# Risc_V.net
KiCad netlist of a schematic drawn in Altium Designer
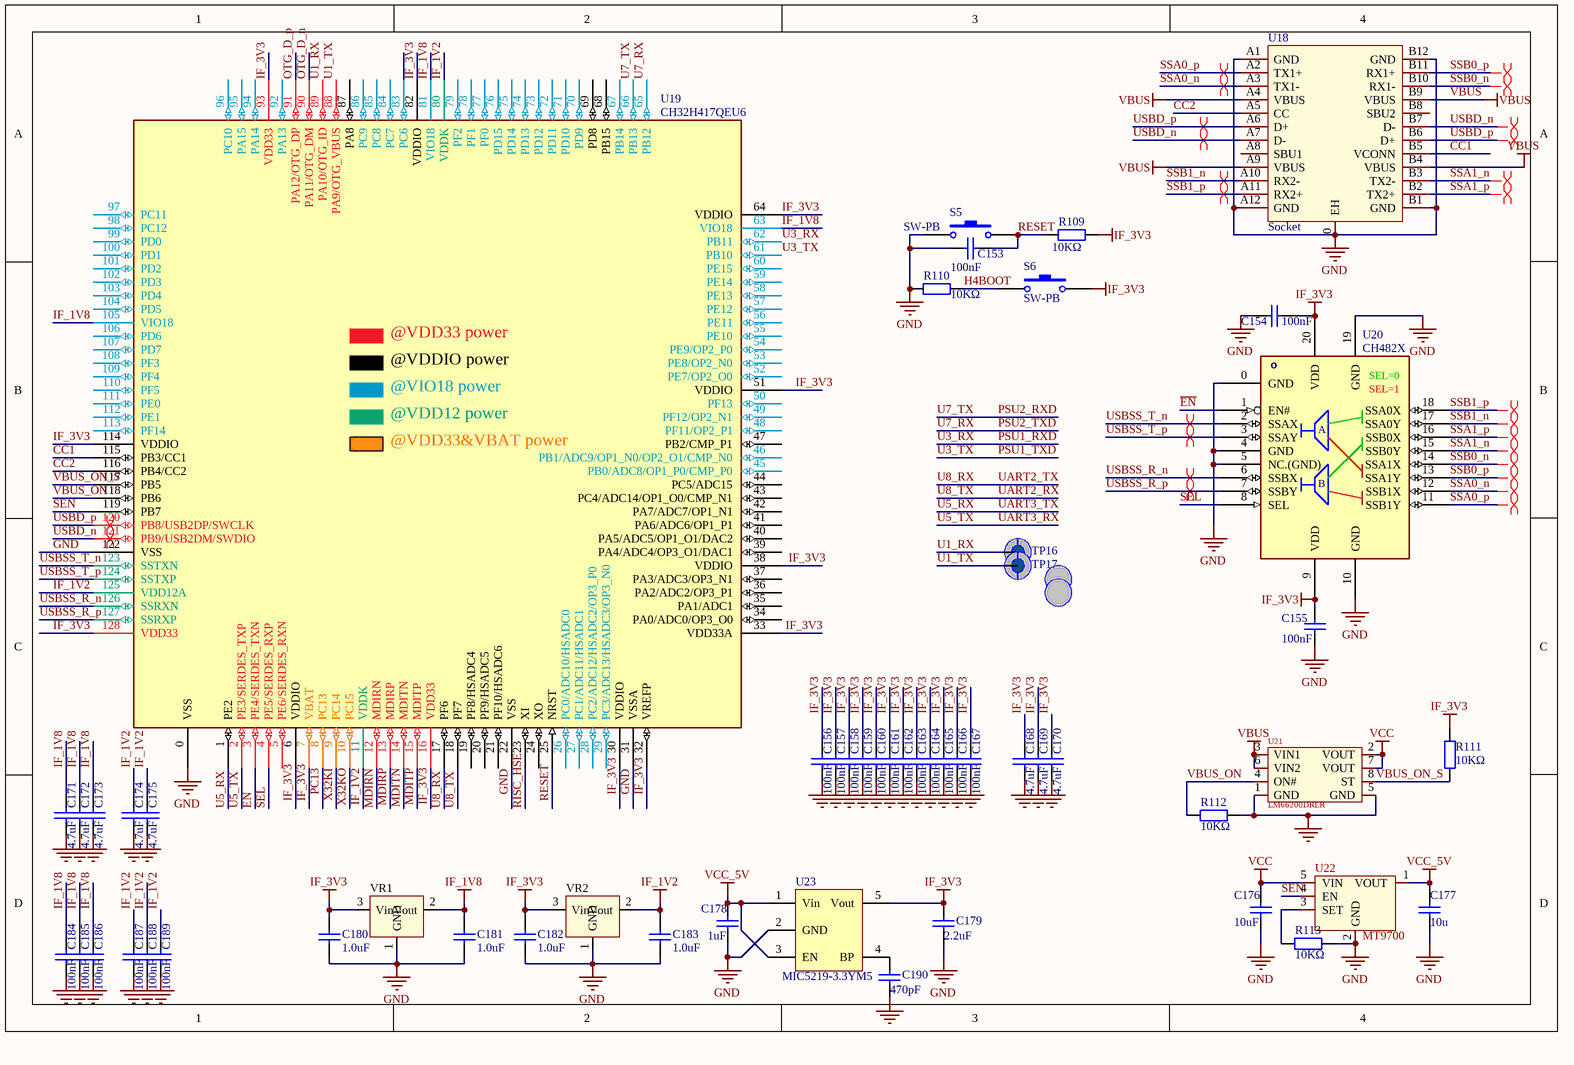
[diagram p0: Risc_V.SchDoc]

(export (version "E")
  (design (tool "Eeschema 10.0.6"))
  (components
    (comp (ref "C153")
      (value "100nF")
      (footprint "0805_C")
      (description "贴片电容")
      (libsource (lib "Miscellaneous Devices LC") (part "0402 100nF (104) 10% 16V"))
    )
    (comp (ref "C154")
      (value "100nF")
      (footprint "0201")
      (description "贴片电容")
      (libsource (lib "嘉立创标准库") (part "0402 100nF (104) 10% 16V"))
    )
    (comp (ref "C155")
      (value "100nF")
      (footprint "0201")
      (description "贴片电容")
      (libsource (lib "嘉立创标准库") (part "0402 100nF (104) 10% 16V"))
    )
    (comp (ref "C156")
      (value "100nF")
      (footprint "0201")
      (description "贴片电容")
      (libsource (lib "嘉立创标准库") (part "0402 100nF (104) 10% 16V"))
    )
    (comp (ref "C157")
      (value "100nF")
      (footprint "0201")
      (description "贴片电容")
      (libsource (lib "嘉立创标准库") (part "0402 100nF (104) 10% 16V"))
    )
    (comp (ref "C158")
      (value "100nF")
      (footprint "0201")
      (description "贴片电容")
      (libsource (lib "嘉立创标准库") (part "0402 100nF (104) 10% 16V"))
    )
    (comp (ref "C159")
      (value "100nF")
      (footprint "0201")
      (description "贴片电容")
      (libsource (lib "嘉立创标准库") (part "0402 100nF (104) 10% 16V"))
    )
    (comp (ref "C160")
      (value "100nF")
      (footprint "0201")
      (description "贴片电容")
      (libsource (lib "嘉立创标准库") (part "0402 100nF (104) 10% 16V"))
    )
    (comp (ref "C161")
      (value "100nF")
      (footprint "0201")
      (description "贴片电容")
      (libsource (lib "嘉立创标准库") (part "0402 100nF (104) 10% 16V"))
    )
    (comp (ref "C162")
      (value "100nF")
      (footprint "0201")
      (description "贴片电容")
      (libsource (lib "嘉立创标准库") (part "0402 100nF (104) 10% 16V"))
    )
    (comp (ref "C163")
      (value "100nF")
      (footprint "0201")
      (description "贴片电容")
      (libsource (lib "嘉立创标准库") (part "0402 100nF (104) 10% 16V"))
    )
    (comp (ref "C164")
      (value "100nF")
      (footprint "0201")
      (description "贴片电容")
      (libsource (lib "嘉立创标准库") (part "0402 100nF (104) 10% 16V"))
    )
    (comp (ref "C165")
      (value "100nF")
      (footprint "0201")
      (description "贴片电容")
      (libsource (lib "嘉立创标准库") (part "0402 100nF (104) 10% 16V"))
    )
    (comp (ref "C166")
      (value "100nF")
      (footprint "0201")
      (description "贴片电容")
      (libsource (lib "嘉立创标准库") (part "0402 100nF (104) 10% 16V"))
    )
    (comp (ref "C167")
      (value "100nF")
      (footprint "0201")
      (description "贴片电容")
      (libsource (lib "嘉立创标准库") (part "0402 100nF (104) 10% 16V"))
    )
    (comp (ref "C168")
      (value "4.7uF")
      (footprint "0805_C")
      (description "Capacitor")
      (libsource (lib "*") (part "CAP"))
    )
    (comp (ref "C169")
      (value "4.7uF")
      (footprint "0805_C")
      (description "Capacitor")
      (libsource (lib "*") (part "CAP"))
    )
    (comp (ref "C170")
      (value "4.7uF")
      (footprint "0805_C")
      (description "Capacitor")
      (libsource (lib "*") (part "CAP"))
    )
    (comp (ref "C171")
      (value "4.7uF")
      (footprint "0805_C")
      (description "Capacitor")
      (libsource (lib "*") (part "CAP"))
    )
    (comp (ref "C172")
      (value "4.7uF")
      (footprint "0805_C")
      (description "Capacitor")
      (libsource (lib "*") (part "CAP"))
    )
    (comp (ref "C173")
      (value "4.7uF")
      (footprint "0805_C")
      (description "Capacitor")
      (libsource (lib "*") (part "CAP"))
    )
    (comp (ref "C174")
      (value "4.7uF")
      (footprint "0805_C")
      (description "Capacitor")
      (libsource (lib "*") (part "CAP"))
    )
    (comp (ref "C175")
      (value "4.7uF")
      (footprint "0805_C")
      (description "Capacitor")
      (libsource (lib "*") (part "CAP"))
    )
    (comp (ref "C176")
      (value "10uF")
      (footprint "0805_C")
      (description "贴片电容")
      (libsource (lib "Miscellaneous Devices LC") (part "0805 10uF (106) 10% 25V"))
    )
    (comp (ref "C177")
      (value "10u")
      (footprint "0805_C")
      (description "贴片电容")
      (libsource (lib "Miscellaneous Devices LC") (part "0805 10uF (106) 10% 25V"))
    )
    (comp (ref "C178")
      (value "1uF")
      (footprint "0805_C")
      (description "贴片电容")
      (libsource (lib "Miscellaneous Devices LC") (part "0805 1uF (105) 10% 50V"))
    )
    (comp (ref "C179")
      (value "2.2uF")
      (footprint "0805_C")
      (description "贴片电容")
      (libsource (lib "Miscellaneous Devices LC") (part "0805 1uF (105) 10% 50V"))
    )
    (comp (ref "C180")
      (value "1.0uF")
      (footprint "0805_C")
      (description "贴片电容")
      (libsource (lib "Miscellaneous Devices LC") (part "0402 1.0uF (105) 10% 25V"))
    )
    (comp (ref "C181")
      (value "1.0uF")
      (footprint "0805_C")
      (description "贴片电容")
      (libsource (lib "Miscellaneous Devices LC") (part "0402 1.0uF (105) 10% 25V"))
    )
    (comp (ref "C182")
      (value "1.0uF")
      (footprint "0805_C")
      (description "贴片电容")
      (libsource (lib "Miscellaneous Devices LC") (part "0402 1.0uF (105) 10% 25V"))
    )
    (comp (ref "C183")
      (value "1.0uF")
      (footprint "0805_C")
      (description "贴片电容")
      (libsource (lib "Miscellaneous Devices LC") (part "0402 1.0uF (105) 10% 25V"))
    )
    (comp (ref "C184")
      (value "100nF")
      (footprint "0201")
      (description "贴片电容")
      (libsource (lib "嘉立创标准库") (part "0402 100nF (104) 10% 16V"))
    )
    (comp (ref "C185")
      (value "100nF")
      (footprint "0201")
      (description "贴片电容")
      (libsource (lib "嘉立创标准库") (part "0402 100nF (104) 10% 16V"))
    )
    (comp (ref "C186")
      (value "100nF")
      (footprint "0201")
      (description "贴片电容")
      (libsource (lib "嘉立创标准库") (part "0402 100nF (104) 10% 16V"))
    )
    (comp (ref "C187")
      (value "100nF")
      (footprint "0201")
      (description "贴片电容")
      (libsource (lib "嘉立创标准库") (part "0402 100nF (104) 10% 16V"))
    )
    (comp (ref "C188")
      (value "100nF")
      (footprint "0201")
      (description "贴片电容")
      (libsource (lib "嘉立创标准库") (part "0402 100nF (104) 10% 16V"))
    )
    (comp (ref "C189")
      (value "100nF")
      (footprint "0201")
      (description "贴片电容")
      (libsource (lib "嘉立创标准库") (part "0402 100nF (104) 10% 16V"))
    )
    (comp (ref "C190")
      (value "470pF")
      (footprint "0805_C")
      (description "贴片电容")
      (libsource (lib "Miscellaneous Devices LC") (part "0805 1uF (105) 10% 50V"))
    )
    (comp (ref "R109")
      (value "10KΩ")
      (footprint "0805_R")
      (description "贴片电阻")
      (libsource (lib "Miscellaneous Devices LC") (part "0402 10KΩ (1002) 1%"))
    )
    (comp (ref "R110")
      (value "10KΩ")
      (footprint "0805_R")
      (description "贴片电阻")
      (libsource (lib "Miscellaneous Devices LC") (part "0402 10KΩ (1002) 1%"))
    )
    (comp (ref "R111")
      (value "10KΩ")
      (footprint "0805_R")
      (description "贴片电阻")
      (libsource (lib "Miscellaneous Devices LC") (part "0805 10KΩ (1002) 1%"))
    )
    (comp (ref "R112")
      (value "10KΩ")
      (footprint "0201")
      (description "贴片电阻")
      (libsource (lib "") (part "0805 10KΩ (1002) 1%_1"))
    )
    (comp (ref "R113")
      (value "10KΩ")
      (footprint "0805_R")
      (description "贴片电阻")
      (libsource (lib "") (part "0805 10KΩ (1002) 1%_1"))
    )
    (comp (ref "S5")
      (value "SW-PB")
      (footprint "SW-3*4-2P")
      (description "Switch")
      (fields (field (name "PUBLISHER") "Altium Limited"))
      (libsource (lib "Miscellaneous Devices") (part "SW-PB"))
    )
    (comp (ref "S6")
      (value "SW-PB")
      (footprint "SW-3*4-2P")
      (description "Switch")
      (fields (field (name "PUBLISHER") "Altium Limited"))
      (libsource (lib "Miscellaneous Devices") (part "SW-PB"))
    )
    (comp (ref "TP16")
      (value "test-point")
      (footprint "POINT")
      (description "测试点")
      (libsource (lib "五向开关") (part "test-point"))
    )
    (comp (ref "TP17")
      (value "test-point")
      (footprint "POINT")
      (description "测试点")
      (libsource (lib "五向开关") (part "test-point"))
    )
    (comp (ref "U18")
      (value "Socket")
      (footprint "USB Type C 24pin全后贴")
      (libsource (lib "五向开关") (part "USB type C 沉板公头"))
    )
    (comp (ref "U19")
      (value "CH32H417QEU6")
      (footprint "QFN128_12.3X12.3")
      (description "RISC-V FPU HD-MCU, 384MHz, USB3.0 & PD, 100M Ethernet, DVP, SDMMC, QSPI, OPA, ADC, DAC")
      (libsource (lib "DHXXXSCH") (part "CH32H417QET6"))
    )
    (comp (ref "U20")
      (value "CH482X")
      (footprint "QFN20_2.5X4.5")
      (description "DP/PCIe/SATA/USB3.0/USB3.2 Differential Switch, QPDT")
      (libsource (lib "CHXXX") (part "CH482X"))
    )
    (comp (ref "U21")
      (value "LM66200DRLR")
      (footprint "SOT-583-8_L2.1-W1.2-P0.50-LS1.6-BL")
      (description "理想二极管")
      (fields (field (name "MANUFACTURER") "TI(德州仪器)"))
      (libsource (lib "五向开关") (part "LM66200DRLR"))
    )
    (comp (ref "U22")
      (value "MT9700")
      (footprint "SOT-23-5")
      (fields (field (name "MANUFACTURER") "西安航天民芯"))
      (libsource (lib "五向开关") (part "MT9700"))
    )
    (comp (ref "U23")
      (value "MIC5219-3.3YM5")
      (footprint "SOT-23-5")
      (description "3.3v低压差稳压芯片")
      (libsource (lib "五向开关") (part "RT9193-33"))
    )
    (comp (ref "VR1")
      (value "XC6206P332MR-G")
      (footprint "SOT-23-3_L2.9-W1.6-P1.90-LS2.8-BR")
      (description "通用LDO")
      (fields (field (name "MANUFACTURER") "TOREX(特瑞仕)"))
      (libsource (lib "五向开关") (part "XC6206P332MR-G_C5446"))
    )
    (comp (ref "VR2")
      (value "XC6206P332MR-G")
      (footprint "SOT-23-3_L2.9-W1.6-P1.90-LS2.8-BR")
      (description "通用LDO")
      (fields (field (name "MANUFACTURER") "TOREX(特瑞仕)"))
      (libsource (lib "五向开关") (part "XC6206P332MR-G_C5446"))
    )
  )
  (nets
    (net (code "1") (name "/CC1") (class "Default")
      (node (ref "U18") (pin "B5") (pinfunction "VCONN_B5") (pintype "passive"))
      (node (ref "U19") (pin "115") (pinfunction "PB3/CC1_115") (pintype "bidirectional"))
    )
    (net (code "2") (name "/CC2") (class "Default")
      (node (ref "U18") (pin "A5") (pinfunction "CC_A5") (pintype "passive"))
      (node (ref "U19") (pin "116") (pinfunction "PB4/CC2_116") (pintype "bidirectional"))
    )
    (net (code "3") (name "/H4BOOT") (class "Default")
      (node (ref "R110") (pin "2") (pinfunction "2_2") (pintype "passive"))
      (node (ref "S6") (pin "1") (pinfunction "1_1") (pintype "passive"))
    )
    (net (code "4") (name "/MDIRN") (class "Default")
      (node (ref "U19") (pin "12") (pinfunction "MDIRN_12") (pintype "bidirectional"))
    )
    (net (code "5") (name "/MDIRP") (class "Default")
      (node (ref "U19") (pin "13") (pinfunction "MDIRP_13") (pintype "bidirectional"))
    )
    (net (code "6") (name "/MDITN") (class "Default")
      (node (ref "U19") (pin "14") (pinfunction "MDITN_14") (pintype "bidirectional"))
    )
    (net (code "7") (name "/MDITP") (class "Default")
      (node (ref "U19") (pin "15") (pinfunction "MDITP_15") (pintype "bidirectional"))
    )
    (net (code "8") (name "/OTG_D_n") (class "Default")
      (node (ref "U19") (pin "90") (pinfunction "PA11/OTG_DM_90") (pintype "bidirectional"))
    )
    (net (code "9") (name "/OTG_D_p") (class "Default")
      (node (ref "U19") (pin "91") (pinfunction "PA12/OTG_DP_91") (pintype "bidirectional"))
    )
    (net (code "10") (name "/PC13") (class "Default")
      (node (ref "U19") (pin "8") (pinfunction "PC13_8") (pintype "bidirectional"))
    )
    (net (code "11") (name "/PSU1_RXD") (class "Default")
      (node (ref "U19") (pin "62") (pinfunction "PB11_62") (pintype "bidirectional"))
    )
    (net (code "12") (name "/PSU1_TXD") (class "Default")
      (node (ref "U19") (pin "61") (pinfunction "PB10_61") (pintype "bidirectional"))
    )
    (net (code "13") (name "/PSU2_RXD") (class "Default")
      (node (ref "U19") (pin "66") (pinfunction "PB13_66") (pintype "bidirectional"))
    )
    (net (code "14") (name "/PSU2_TXD") (class "Default")
      (node (ref "U19") (pin "65") (pinfunction "PB12_65") (pintype "bidirectional"))
    )
    (net (code "15") (name "/RESET") (class "Default")
      (node (ref "C153") (pin "2") (pinfunction "2_2") (pintype "passive"))
      (node (ref "R109") (pin "1") (pinfunction "1_1") (pintype "passive"))
      (node (ref "S5") (pin "2") (pinfunction "2_2") (pintype "passive"))
      (node (ref "U19") (pin "25") (pinfunction "NRST_25") (pintype "input"))
    )
    (net (code "16") (name "/RISC_HSE") (class "Default")
      (node (ref "U19") (pin "23") (pinfunction "XI_23") (pintype "bidirectional"))
    )
    (net (code "17") (name "/SEL") (class "Default")
      (node (ref "U19") (pin "4") (pinfunction "PE5/SERDES_RXP_4") (pintype "bidirectional"))
      (node (ref "U20") (pin "8") (pinfunction "SEL_8") (pintype "input"))
    )
    (net (code "18") (name "/SEN") (class "Default")
      (node (ref "U19") (pin "119") (pinfunction "PB7_119") (pintype "bidirectional"))
      (node (ref "U22") (pin "4") (pinfunction "EN_4") (pintype "passive"))
    )
    (net (code "19") (name "/SSA0_n") (class "Default")
      (node (ref "U18") (pin "A3") (pinfunction "TX1-_A3") (pintype "passive"))
      (node (ref "U20") (pin "12") (pinfunction "SSB1X_12") (pintype "bidirectional"))
    )
    (net (code "20") (name "/SSA0_p") (class "Default")
      (node (ref "U18") (pin "A2") (pinfunction "TX1+_A2") (pintype "passive"))
      (node (ref "U20") (pin "11") (pinfunction "SSB1Y_11") (pintype "bidirectional"))
    )
    (net (code "21") (name "/SSA1_n") (class "Default")
      (node (ref "U18") (pin "B3") (pinfunction "TX2-_B3") (pintype "passive"))
      (node (ref "U20") (pin "15") (pinfunction "SSB0Y_15") (pintype "bidirectional"))
    )
    (net (code "22") (name "/SSA1_p") (class "Default")
      (node (ref "U18") (pin "B2") (pinfunction "TX2+_B2") (pintype "passive"))
      (node (ref "U20") (pin "16") (pinfunction "SSB0X_16") (pintype "bidirectional"))
    )
    (net (code "23") (name "/SSB0_n") (class "Default")
      (node (ref "U18") (pin "B10") (pinfunction "RX1-_B10") (pintype "passive"))
      (node (ref "U20") (pin "14") (pinfunction "SSA1X_14") (pintype "bidirectional"))
    )
    (net (code "24") (name "/SSB0_p") (class "Default")
      (node (ref "U18") (pin "B11") (pinfunction "RX1+_B11") (pintype "passive"))
      (node (ref "U20") (pin "13") (pinfunction "SSA1Y_13") (pintype "bidirectional"))
    )
    (net (code "25") (name "/SSB1_n") (class "Default")
      (node (ref "U18") (pin "A10") (pinfunction "RX2-_A10") (pintype "passive"))
      (node (ref "U20") (pin "17") (pinfunction "SSA0Y_17") (pintype "bidirectional"))
    )
    (net (code "26") (name "/SSB1_p") (class "Default")
      (node (ref "U18") (pin "A11") (pinfunction "RX2+_A11") (pintype "passive"))
      (node (ref "U20") (pin "18") (pinfunction "SSA0X_18") (pintype "bidirectional"))
    )
    (net (code "27") (name "/U1_RX") (class "Default")
      (node (ref "TP16") (pin "1") (pinfunction "point_1") (pintype "passive"))
      (node (ref "U19") (pin "89") (pinfunction "PA10/OTG_ID_89") (pintype "bidirectional"))
    )
    (net (code "28") (name "/U1_TX") (class "Default")
      (node (ref "TP17") (pin "1") (pinfunction "point_1") (pintype "passive"))
      (node (ref "U19") (pin "88") (pinfunction "PA9/OTG_VBUS_88") (pintype "bidirectional"))
    )
    (net (code "29") (name "/U5_RX") (class "Default")
      (node (ref "U19") (pin "1") (pinfunction "PE2_1") (pintype "bidirectional"))
    )
    (net (code "30") (name "/U5_TX") (class "Default")
      (node (ref "U19") (pin "2") (pinfunction "PE3/SERDES_TXP_2") (pintype "bidirectional"))
    )
    (net (code "31") (name "/U8_RX") (class "Default")
      (node (ref "U19") (pin "17") (pinfunction "PF6_17") (pintype "bidirectional"))
    )
    (net (code "32") (name "/U8_TX") (class "Default")
      (node (ref "U19") (pin "18") (pinfunction "PF7_18") (pintype "bidirectional"))
    )
    (net (code "33") (name "/USBD_n") (class "Default")
      (node (ref "U18") (pin "A7") (pinfunction "D-_A7") (pintype "passive"))
      (node (ref "U18") (pin "B7") (pinfunction "D-_B7") (pintype "passive"))
      (node (ref "U19") (pin "121") (pinfunction "PB9/USB2DM/SWDIO_121") (pintype "bidirectional"))
    )
    (net (code "34") (name "/USBD_p") (class "Default")
      (node (ref "U18") (pin "A6") (pinfunction "D+_A6") (pintype "passive"))
      (node (ref "U18") (pin "B6") (pinfunction "D+_B6") (pintype "passive"))
      (node (ref "U19") (pin "120") (pinfunction "PB8/USB2DP/SWCLK_120") (pintype "bidirectional"))
    )
    (net (code "35") (name "/USBSS_R_n") (class "Default")
      (node (ref "U19") (pin "126") (pinfunction "SSRXN_126") (pintype "bidirectional"))
      (node (ref "U20") (pin "6") (pinfunction "SSBX_6") (pintype "bidirectional"))
    )
    (net (code "36") (name "/USBSS_R_p") (class "Default")
      (node (ref "U19") (pin "127") (pinfunction "SSRXP_127") (pintype "bidirectional"))
      (node (ref "U20") (pin "7") (pinfunction "SSBY_7") (pintype "bidirectional"))
    )
    (net (code "37") (name "/USBSS_T_n") (class "Default")
      (node (ref "U19") (pin "123") (pinfunction "SSTXN_123") (pintype "bidirectional"))
      (node (ref "U20") (pin "2") (pinfunction "SSAX_2") (pintype "bidirectional"))
    )
    (net (code "38") (name "/USBSS_T_p") (class "Default")
      (node (ref "U19") (pin "124") (pinfunction "SSTXP_124") (pintype "bidirectional"))
      (node (ref "U20") (pin "3") (pinfunction "SSAY_3") (pintype "bidirectional"))
    )
    (net (code "39") (name "/VBUS_ON") (class "Default")
      (node (ref "R112") (pin "2") (pinfunction "2_2") (pintype "passive"))
      (node (ref "U19") (pin "118") (pinfunction "PB6_118") (pintype "bidirectional"))
      (node (ref "U21") (pin "4") (pinfunction "ON#_4") (pintype "passive"))
    )
    (net (code "40") (name "/VBUS_ON_S") (class "Default")
      (node (ref "R111") (pin "1") (pinfunction "1_1") (pintype "passive"))
      (node (ref "U19") (pin "117") (pinfunction "PB5_117") (pintype "bidirectional"))
      (node (ref "U21") (pin "8") (pinfunction "ST_8") (pintype "passive"))
    )
    (net (code "41") (name "/X32KI") (class "Default")
      (node (ref "U19") (pin "9") (pinfunction "PC14_9") (pintype "bidirectional"))
    )
    (net (code "42") (name "/X32KO") (class "Default")
      (node (ref "U19") (pin "10") (pinfunction "PC15_10") (pintype "bidirectional"))
    )
    (net (code "43") (name "/~{EN}") (class "Default")
      (node (ref "U19") (pin "3") (pinfunction "PE4/SERDES_TXN_3") (pintype "bidirectional"))
      (node (ref "U20") (pin "1") (pinfunction "EN#_1") (pintype "input"))
    )
    (net (code "44") (name "GND") (class "Default")
      (node (ref "C153") (pin "1") (pinfunction "1_1") (pintype "passive"))
      (node (ref "C154") (pin "2") (pinfunction "2_2") (pintype "passive"))
      (node (ref "C155") (pin "1") (pinfunction "1_1") (pintype "passive"))
      (node (ref "C156") (pin "2") (pinfunction "2_2") (pintype "passive"))
      (node (ref "C157") (pin "1") (pinfunction "1_1") (pintype "passive"))
      (node (ref "C158") (pin "2") (pinfunction "2_2") (pintype "passive"))
      (node (ref "C159") (pin "2") (pinfunction "2_2") (pintype "passive"))
      (node (ref "C160") (pin "1") (pinfunction "1_1") (pintype "passive"))
      (node (ref "C161") (pin "2") (pinfunction "2_2") (pintype "passive"))
      (node (ref "C162") (pin "1") (pinfunction "1_1") (pintype "passive"))
      (node (ref "C163") (pin "2") (pinfunction "2_2") (pintype "passive"))
      (node (ref "C164") (pin "2") (pinfunction "2_2") (pintype "passive"))
      (node (ref "C165") (pin "1") (pinfunction "1_1") (pintype "passive"))
      (node (ref "C166") (pin "1") (pinfunction "1_1") (pintype "passive"))
      (node (ref "C167") (pin "1") (pinfunction "1_1") (pintype "passive"))
      (node (ref "C168") (pin "2") (pinfunction "2_2") (pintype "passive"))
      (node (ref "C169") (pin "2") (pinfunction "2_2") (pintype "passive"))
      (node (ref "C170") (pin "2") (pinfunction "2_2") (pintype "passive"))
      (node (ref "C171") (pin "2") (pinfunction "2_2") (pintype "passive"))
      (node (ref "C172") (pin "1") (pinfunction "1_1") (pintype "passive"))
      (node (ref "C173") (pin "2") (pinfunction "2_2") (pintype "passive"))
      (node (ref "C174") (pin "2") (pinfunction "2_2") (pintype "passive"))
      (node (ref "C175") (pin "1") (pinfunction "1_1") (pintype "passive"))
      (node (ref "C176") (pin "1") (pinfunction "1_1") (pintype "passive"))
      (node (ref "C177") (pin "1") (pinfunction "1_1") (pintype "passive"))
      (node (ref "C178") (pin "1") (pinfunction "1_1") (pintype "passive"))
      (node (ref "C179") (pin "1") (pinfunction "1_1") (pintype "passive"))
      (node (ref "C180") (pin "1") (pinfunction "1_1") (pintype "passive"))
      (node (ref "C181") (pin "1") (pinfunction "1_1") (pintype "passive"))
      (node (ref "C182") (pin "1") (pinfunction "1_1") (pintype "passive"))
      (node (ref "C183") (pin "1") (pinfunction "1_1") (pintype "passive"))
      (node (ref "C184") (pin "1") (pinfunction "1_1") (pintype "passive"))
      (node (ref "C185") (pin "1") (pinfunction "1_1") (pintype "passive"))
      (node (ref "C186") (pin "2") (pinfunction "2_2") (pintype "passive"))
      (node (ref "C187") (pin "1") (pinfunction "1_1") (pintype "passive"))
      (node (ref "C188") (pin "1") (pinfunction "1_1") (pintype "passive"))
      (node (ref "C189") (pin "1") (pinfunction "1_1") (pintype "passive"))
      (node (ref "C190") (pin "1") (pinfunction "1_1") (pintype "passive"))
      (node (ref "R110") (pin "1") (pinfunction "1_1") (pintype "passive"))
      (node (ref "R112") (pin "1") (pinfunction "1_1") (pintype "passive"))
      (node (ref "R113") (pin "1") (pinfunction "1_1") (pintype "passive"))
      (node (ref "S5") (pin "1") (pinfunction "1_1") (pintype "passive"))
      (node (ref "U18") (pin "0") (pinfunction "EH_0") (pintype "passive"))
      (node (ref "U18") (pin "A1") (pinfunction "GND_A1") (pintype "passive"))
      (node (ref "U18") (pin "A12") (pinfunction "GND_A12") (pintype "passive"))
      (node (ref "U18") (pin "B1") (pinfunction "GND_B1") (pintype "passive"))
      (node (ref "U18") (pin "B12") (pinfunction "GND_B12") (pintype "passive"))
      (node (ref "U19") (pin "0") (pinfunction "VSS_0") (pintype "power_in"))
      (node (ref "U19") (pin "122") (pinfunction "VSS_122") (pintype "power_in"))
      (node (ref "U19") (pin "22") (pinfunction "VSS_22") (pintype "power_in"))
      (node (ref "U19") (pin "31") (pinfunction "VSSA_31") (pintype "power_in"))
      (node (ref "U20") (pin "0") (pinfunction "GND_0") (pintype "power_in"))
      (node (ref "U20") (pin "10") (pinfunction "GND_10") (pintype "power_in"))
      (node (ref "U20") (pin "19") (pinfunction "GND_19") (pintype "power_in"))
      (node (ref "U20") (pin "4") (pinfunction "GND_4") (pintype "power_in"))
      (node (ref "U20") (pin "5") (pinfunction "NC.(GND)_5") (pintype "passive"))
      (node (ref "U21") (pin "1") (pinfunction "GND_1") (pintype "passive"))
      (node (ref "U21") (pin "5") (pinfunction "GND_5") (pintype "passive"))
      (node (ref "U22") (pin "2") (pinfunction "GND_2") (pintype "passive"))
      (node (ref "U23") (pin "2") (pinfunction "GND_2") (pintype "passive"))
      (node (ref "VR1") (pin "1") (pinfunction "GND_1") (pintype "passive"))
      (node (ref "VR2") (pin "1") (pinfunction "GND_1") (pintype "passive"))
    )
    (net (code "45") (name "IF_1V2") (class "Default")
      (node (ref "C174") (pin "1") (pinfunction "1_1") (pintype "passive"))
      (node (ref "C175") (pin "2") (pinfunction "2_2") (pintype "passive"))
      (node (ref "C183") (pin "2") (pinfunction "2_2") (pintype "passive"))
      (node (ref "C187") (pin "2") (pinfunction "2_2") (pintype "passive"))
      (node (ref "C188") (pin "2") (pinfunction "2_2") (pintype "passive"))
      (node (ref "C189") (pin "2") (pinfunction "2_2") (pintype "passive"))
      (node (ref "U19") (pin "11") (pinfunction "VDDK_11") (pintype "power_in"))
      (node (ref "U19") (pin "125") (pinfunction "VDD12A_125") (pintype "power_in"))
      (node (ref "U19") (pin "80") (pinfunction "VDDK_80") (pintype "power_in"))
      (node (ref "VR2") (pin "2") (pinfunction "Vout_2") (pintype "passive"))
    )
    (net (code "46") (name "IF_1V8") (class "Default")
      (node (ref "C171") (pin "1") (pinfunction "1_1") (pintype "passive"))
      (node (ref "C172") (pin "2") (pinfunction "2_2") (pintype "passive"))
      (node (ref "C173") (pin "1") (pinfunction "1_1") (pintype "passive"))
      (node (ref "C181") (pin "2") (pinfunction "2_2") (pintype "passive"))
      (node (ref "C184") (pin "2") (pinfunction "2_2") (pintype "passive"))
      (node (ref "C185") (pin "2") (pinfunction "2_2") (pintype "passive"))
      (node (ref "C186") (pin "1") (pinfunction "1_1") (pintype "passive"))
      (node (ref "U19") (pin "105") (pinfunction "VIO18_105") (pintype "power_in"))
      (node (ref "U19") (pin "63") (pinfunction "VIO18_63") (pintype "power_in"))
      (node (ref "U19") (pin "81") (pinfunction "VIO18_81") (pintype "power_in"))
      (node (ref "VR1") (pin "2") (pinfunction "Vout_2") (pintype "passive"))
    )
    (net (code "47") (name "IF_3V3") (class "Default")
      (node (ref "C154") (pin "1") (pinfunction "1_1") (pintype "passive"))
      (node (ref "C155") (pin "2") (pinfunction "2_2") (pintype "passive"))
      (node (ref "C156") (pin "1") (pinfunction "1_1") (pintype "passive"))
      (node (ref "C157") (pin "2") (pinfunction "2_2") (pintype "passive"))
      (node (ref "C158") (pin "1") (pinfunction "1_1") (pintype "passive"))
      (node (ref "C159") (pin "1") (pinfunction "1_1") (pintype "passive"))
      (node (ref "C160") (pin "2") (pinfunction "2_2") (pintype "passive"))
      (node (ref "C161") (pin "1") (pinfunction "1_1") (pintype "passive"))
      (node (ref "C162") (pin "2") (pinfunction "2_2") (pintype "passive"))
      (node (ref "C163") (pin "1") (pinfunction "1_1") (pintype "passive"))
      (node (ref "C164") (pin "1") (pinfunction "1_1") (pintype "passive"))
      (node (ref "C165") (pin "2") (pinfunction "2_2") (pintype "passive"))
      (node (ref "C166") (pin "2") (pinfunction "2_2") (pintype "passive"))
      (node (ref "C167") (pin "2") (pinfunction "2_2") (pintype "passive"))
      (node (ref "C168") (pin "1") (pinfunction "1_1") (pintype "passive"))
      (node (ref "C169") (pin "1") (pinfunction "1_1") (pintype "passive"))
      (node (ref "C170") (pin "1") (pinfunction "1_1") (pintype "passive"))
      (node (ref "C179") (pin "2") (pinfunction "2_2") (pintype "passive"))
      (node (ref "C180") (pin "2") (pinfunction "2_2") (pintype "passive"))
      (node (ref "C182") (pin "2") (pinfunction "2_2") (pintype "passive"))
      (node (ref "R109") (pin "2") (pinfunction "2_2") (pintype "passive"))
      (node (ref "R111") (pin "2") (pinfunction "2_2") (pintype "passive"))
      (node (ref "S6") (pin "2") (pinfunction "2_2") (pintype "passive"))
      (node (ref "U19") (pin "114") (pinfunction "VDDIO_114") (pintype "power_in"))
      (node (ref "U19") (pin "128") (pinfunction "VDD33_128") (pintype "power_in"))
      (node (ref "U19") (pin "16") (pinfunction "VDD33_16") (pintype "power_in"))
      (node (ref "U19") (pin "30") (pinfunction "VDDIO_30") (pintype "power_in"))
      (node (ref "U19") (pin "32") (pinfunction "VREFP_32") (pintype "bidirectional"))
      (node (ref "U19") (pin "33") (pinfunction "VDD33A_33") (pintype "power_in"))
      (node (ref "U19") (pin "38") (pinfunction "VDDIO_38") (pintype "power_in"))
      (node (ref "U19") (pin "51") (pinfunction "VDDIO_51") (pintype "power_in"))
      (node (ref "U19") (pin "6") (pinfunction "VDDIO_6") (pintype "power_in"))
      (node (ref "U19") (pin "64") (pinfunction "VDDIO_64") (pintype "power_in"))
      (node (ref "U19") (pin "7") (pinfunction "VBAT_7") (pintype "bidirectional"))
      (node (ref "U19") (pin "82") (pinfunction "VDDIO_82") (pintype "power_in"))
      (node (ref "U19") (pin "93") (pinfunction "VDD33_93") (pintype "power_in"))
      (node (ref "U20") (pin "20") (pinfunction "VDD_20") (pintype "power_in"))
      (node (ref "U20") (pin "9") (pinfunction "VDD_9") (pintype "power_in"))
      (node (ref "U23") (pin "5") (pinfunction "Vout_5") (pintype "passive"))
      (node (ref "VR1") (pin "3") (pinfunction "Vin_3") (pintype "passive"))
      (node (ref "VR2") (pin "3") (pinfunction "Vin_3") (pintype "passive"))
    )
    (net (code "48") (name "Net-(U22-SET)") (class "Default")
      (node (ref "R113") (pin "2") (pinfunction "2_2") (pintype "passive"))
      (node (ref "U22") (pin "3") (pinfunction "SET_3") (pintype "passive"))
    )
    (net (code "49") (name "Net-(U23-BP)") (class "Default")
      (node (ref "C190") (pin "2") (pinfunction "2_2") (pintype "passive"))
      (node (ref "U23") (pin "4") (pinfunction "BP_4") (pintype "passive"))
    )
    (net (code "50") (name "VBUS") (class "Default")
      (node (ref "U18") (pin "A4") (pinfunction "VBUS_A4") (pintype "passive"))
      (node (ref "U18") (pin "A9") (pinfunction "VBUS_A9") (pintype "passive"))
      (node (ref "U18") (pin "B4") (pinfunction "VBUS_B4") (pintype "passive"))
      (node (ref "U18") (pin "B9") (pinfunction "VBUS_B9") (pintype "passive"))
      (node (ref "U21") (pin "3") (pinfunction "VIN1_3") (pintype "passive"))
      (node (ref "U21") (pin "6") (pinfunction "VIN2_6") (pintype "passive"))
    )
    (net (code "51") (name "VCC") (class "Default")
      (node (ref "C176") (pin "2") (pinfunction "2_2") (pintype "passive"))
      (node (ref "U21") (pin "2") (pinfunction "VOUT_2") (pintype "passive"))
      (node (ref "U21") (pin "7") (pinfunction "VOUT_7") (pintype "passive"))
      (node (ref "U22") (pin "5") (pinfunction "VIN_5") (pintype "passive"))
    )
    (net (code "52") (name "VCC_5V") (class "Default")
      (node (ref "C177") (pin "2") (pinfunction "2_2") (pintype "passive"))
      (node (ref "C178") (pin "2") (pinfunction "2_2") (pintype "passive"))
      (node (ref "U22") (pin "1") (pinfunction "VOUT_1") (pintype "passive"))
      (node (ref "U23") (pin "1") (pinfunction "Vin_1") (pintype "passive"))
      (node (ref "U23") (pin "3") (pinfunction "EN_3") (pintype "passive"))
    )
    (net (code "53") (name "unconnected-(U18-SBU1-PadA8)") (class "Default")
      (node (ref "U18") (pin "A8") (pinfunction "SBU1_A8") (pintype "passive"))
    )
    (net (code "54") (name "unconnected-(U18-SBU2-PadB8)") (class "Default")
      (node (ref "U18") (pin "B8") (pinfunction "SBU2_B8") (pintype "passive"))
    )
    (net (code "55") (name "unconnected-(U19-PA0{slash}ADC0{slash}OP3_O0-Pad34)") (class "Default")
      (node (ref "U19") (pin "34") (pinfunction "PA0/ADC0/OP3_O0_34") (pintype "bidirectional"))
    )
    (net (code "56") (name "unconnected-(U19-PA1{slash}ADC1-Pad35)") (class "Default")
      (node (ref "U19") (pin "35") (pinfunction "PA1/ADC1_35") (pintype "bidirectional"))
    )
    (net (code "57") (name "unconnected-(U19-PA2{slash}ADC2{slash}OP3_P1-Pad36)") (class "Default")
      (node (ref "U19") (pin "36") (pinfunction "PA2/ADC2/OP3_P1_36") (pintype "bidirectional"))
    )
    (net (code "58") (name "unconnected-(U19-PA3{slash}ADC3{slash}OP3_N1-Pad37)") (class "Default")
      (node (ref "U19") (pin "37") (pinfunction "PA3/ADC3/OP3_N1_37") (pintype "bidirectional"))
    )
    (net (code "59") (name "unconnected-(U19-PA4{slash}ADC4{slash}OP3_O1{slash}DAC1-Pad39)") (class "Default")
      (node (ref "U19") (pin "39") (pinfunction "PA4/ADC4/OP3_O1/DAC1_39") (pintype "bidirectional"))
    )
    (net (code "60") (name "unconnected-(U19-PA5{slash}ADC5{slash}OP1_O1{slash}DAC2-Pad40)") (class "Default")
      (node (ref "U19") (pin "40") (pinfunction "PA5/ADC5/OP1_O1/DAC2_40") (pintype "bidirectional"))
    )
    (net (code "61") (name "unconnected-(U19-PA6{slash}ADC6{slash}OP1_P1-Pad41)") (class "Default")
      (node (ref "U19") (pin "41") (pinfunction "PA6/ADC6/OP1_P1_41") (pintype "bidirectional"))
    )
    (net (code "62") (name "unconnected-(U19-PA7{slash}ADC7{slash}OP1_N1-Pad42)") (class "Default")
      (node (ref "U19") (pin "42") (pinfunction "PA7/ADC7/OP1_N1_42") (pintype "bidirectional"))
    )
    (net (code "63") (name "unconnected-(U19-PA8-Pad87)") (class "Default")
      (node (ref "U19") (pin "87") (pinfunction "PA8_87") (pintype "bidirectional"))
    )
    (net (code "64") (name "unconnected-(U19-PA13-Pad92)") (class "Default")
      (node (ref "U19") (pin "92") (pinfunction "PA13_92") (pintype "bidirectional"))
    )
    (net (code "65") (name "unconnected-(U19-PA14-Pad94)") (class "Default")
      (node (ref "U19") (pin "94") (pinfunction "PA14_94") (pintype "bidirectional"))
    )
    (net (code "66") (name "unconnected-(U19-PA15-Pad95)") (class "Default")
      (node (ref "U19") (pin "95") (pinfunction "PA15_95") (pintype "bidirectional"))
    )
    (net (code "67") (name "unconnected-(U19-PB0{slash}ADC8{slash}OP1_P0{slash}CMP_P0-Pad45)") (class "Default")
      (node (ref "U19") (pin "45") (pinfunction "PB0/ADC8/OP1_P0/CMP_P0_45") (pintype "bidirectional"))
    )
    (net (code "68") (name "unconnected-(U19-PB1{slash}ADC9{slash}OP1_N0{slash}OP2_O1{slash}CMP_N0-Pad46)") (class "Default")
      (node (ref "U19") (pin "46") (pinfunction "PB1/ADC9/OP1_N0/OP2_O1/CMP_N0_46") (pintype "bidirectional"))
    )
    (net (code "69") (name "unconnected-(U19-PB2{slash}CMP_P1-Pad47)") (class "Default")
      (node (ref "U19") (pin "47") (pinfunction "PB2/CMP_P1_47") (pintype "bidirectional"))
    )
    (net (code "70") (name "unconnected-(U19-PB14-Pad67)") (class "Default")
      (node (ref "U19") (pin "67") (pinfunction "PB14_67") (pintype "bidirectional"))
    )
    (net (code "71") (name "unconnected-(U19-PB15-Pad68)") (class "Default")
      (node (ref "U19") (pin "68") (pinfunction "PB15_68") (pintype "bidirectional"))
    )
    (net (code "72") (name "unconnected-(U19-PC0{slash}ADC10{slash}HSADC0-Pad26)") (class "Default")
      (node (ref "U19") (pin "26") (pinfunction "PC0/ADC10/HSADC0_26") (pintype "bidirectional"))
    )
    (net (code "73") (name "unconnected-(U19-PC1{slash}ADC11{slash}HSADC1-Pad27)") (class "Default")
      (node (ref "U19") (pin "27") (pinfunction "PC1/ADC11/HSADC1_27") (pintype "bidirectional"))
    )
    (net (code "74") (name "unconnected-(U19-PC2{slash}ADC12{slash}HSADC2{slash}OP3_P0-Pad28)") (class "Default")
      (node (ref "U19") (pin "28") (pinfunction "PC2/ADC12/HSADC2/OP3_P0_28") (pintype "bidirectional"))
    )
    (net (code "75") (name "unconnected-(U19-PC3{slash}ADC13{slash}HSADC3{slash}OP3_N0-Pad29)") (class "Default")
      (node (ref "U19") (pin "29") (pinfunction "PC3/ADC13/HSADC3/OP3_N0_29") (pintype "bidirectional"))
    )
    (net (code "76") (name "unconnected-(U19-PC4{slash}ADC14{slash}OP1_O0{slash}CMP_N1-Pad43)") (class "Default")
      (node (ref "U19") (pin "43") (pinfunction "PC4/ADC14/OP1_O0/CMP_N1_43") (pintype "bidirectional"))
    )
    (net (code "77") (name "unconnected-(U19-PC5{slash}ADC15-Pad44)") (class "Default")
      (node (ref "U19") (pin "44") (pinfunction "PC5/ADC15_44") (pintype "bidirectional"))
    )
    (net (code "78") (name "unconnected-(U19-PC6-Pad83)") (class "Default")
      (node (ref "U19") (pin "83") (pinfunction "PC6_83") (pintype "bidirectional"))
    )
    (net (code "79") (name "unconnected-(U19-PC7-Pad84)") (class "Default")
      (node (ref "U19") (pin "84") (pinfunction "PC7_84") (pintype "bidirectional"))
    )
    (net (code "80") (name "unconnected-(U19-PC8-Pad85)") (class "Default")
      (node (ref "U19") (pin "85") (pinfunction "PC8_85") (pintype "bidirectional"))
    )
    (net (code "81") (name "unconnected-(U19-PC9-Pad86)") (class "Default")
      (node (ref "U19") (pin "86") (pinfunction "PC9_86") (pintype "bidirectional"))
    )
    (net (code "82") (name "unconnected-(U19-PC10-Pad96)") (class "Default")
      (node (ref "U19") (pin "96") (pinfunction "PC10_96") (pintype "bidirectional"))
    )
    (net (code "83") (name "unconnected-(U19-PC11-Pad97)") (class "Default")
      (node (ref "U19") (pin "97") (pinfunction "PC11_97") (pintype "bidirectional"))
    )
    (net (code "84") (name "unconnected-(U19-PC12-Pad98)") (class "Default")
      (node (ref "U19") (pin "98") (pinfunction "PC12_98") (pintype "bidirectional"))
    )
    (net (code "85") (name "unconnected-(U19-PD0-Pad99)") (class "Default")
      (node (ref "U19") (pin "99") (pinfunction "PD0_99") (pintype "bidirectional"))
    )
    (net (code "86") (name "unconnected-(U19-PD1-Pad100)") (class "Default")
      (node (ref "U19") (pin "100") (pinfunction "PD1_100") (pintype "bidirectional"))
    )
    (net (code "87") (name "unconnected-(U19-PD2-Pad101)") (class "Default")
      (node (ref "U19") (pin "101") (pinfunction "PD2_101") (pintype "bidirectional"))
    )
    (net (code "88") (name "unconnected-(U19-PD3-Pad102)") (class "Default")
      (node (ref "U19") (pin "102") (pinfunction "PD3_102") (pintype "bidirectional"))
    )
    (net (code "89") (name "unconnected-(U19-PD4-Pad103)") (class "Default")
      (node (ref "U19") (pin "103") (pinfunction "PD4_103") (pintype "bidirectional"))
    )
    (net (code "90") (name "unconnected-(U19-PD5-Pad104)") (class "Default")
      (node (ref "U19") (pin "104") (pinfunction "PD5_104") (pintype "bidirectional"))
    )
    (net (code "91") (name "unconnected-(U19-PD6-Pad106)") (class "Default")
      (node (ref "U19") (pin "106") (pinfunction "PD6_106") (pintype "bidirectional"))
    )
    (net (code "92") (name "unconnected-(U19-PD7-Pad107)") (class "Default")
      (node (ref "U19") (pin "107") (pinfunction "PD7_107") (pintype "bidirectional"))
    )
    (net (code "93") (name "unconnected-(U19-PD8-Pad69)") (class "Default")
      (node (ref "U19") (pin "69") (pinfunction "PD8_69") (pintype "bidirectional"))
    )
    (net (code "94") (name "unconnected-(U19-PD9-Pad70)") (class "Default")
      (node (ref "U19") (pin "70") (pinfunction "PD9_70") (pintype "bidirectional"))
    )
    (net (code "95") (name "unconnected-(U19-PD10-Pad71)") (class "Default")
      (node (ref "U19") (pin "71") (pinfunction "PD10_71") (pintype "bidirectional"))
    )
    (net (code "96") (name "unconnected-(U19-PD11-Pad72)") (class "Default")
      (node (ref "U19") (pin "72") (pinfunction "PD11_72") (pintype "bidirectional"))
    )
    (net (code "97") (name "unconnected-(U19-PD12-Pad73)") (class "Default")
      (node (ref "U19") (pin "73") (pinfunction "PD12_73") (pintype "bidirectional"))
    )
    (net (code "98") (name "unconnected-(U19-PD13-Pad74)") (class "Default")
      (node (ref "U19") (pin "74") (pinfunction "PD13_74") (pintype "bidirectional"))
    )
    (net (code "99") (name "unconnected-(U19-PD14-Pad75)") (class "Default")
      (node (ref "U19") (pin "75") (pinfunction "PD14_75") (pintype "bidirectional"))
    )
    (net (code "100") (name "unconnected-(U19-PD15-Pad76)") (class "Default")
      (node (ref "U19") (pin "76") (pinfunction "PD15_76") (pintype "bidirectional"))
    )
    (net (code "101") (name "unconnected-(U19-PE0-Pad111)") (class "Default")
      (node (ref "U19") (pin "111") (pinfunction "PE0_111") (pintype "bidirectional"))
    )
    (net (code "102") (name "unconnected-(U19-PE1-Pad112)") (class "Default")
      (node (ref "U19") (pin "112") (pinfunction "PE1_112") (pintype "bidirectional"))
    )
    (net (code "103") (name "unconnected-(U19-PE6{slash}SERDES_RXN-Pad5)") (class "Default")
      (node (ref "U19") (pin "5") (pinfunction "PE6/SERDES_RXN_5") (pintype "bidirectional"))
    )
    (net (code "104") (name "unconnected-(U19-PE7{slash}OP2_O0-Pad52)") (class "Default")
      (node (ref "U19") (pin "52") (pinfunction "PE7/OP2_O0_52") (pintype "bidirectional"))
    )
    (net (code "105") (name "unconnected-(U19-PE8{slash}OP2_N0-Pad53)") (class "Default")
      (node (ref "U19") (pin "53") (pinfunction "PE8/OP2_N0_53") (pintype "bidirectional"))
    )
    (net (code "106") (name "unconnected-(U19-PE9{slash}OP2_P0-Pad54)") (class "Default")
      (node (ref "U19") (pin "54") (pinfunction "PE9/OP2_P0_54") (pintype "bidirectional"))
    )
    (net (code "107") (name "unconnected-(U19-PE10-Pad55)") (class "Default")
      (node (ref "U19") (pin "55") (pinfunction "PE10_55") (pintype "bidirectional"))
    )
    (net (code "108") (name "unconnected-(U19-PE11-Pad56)") (class "Default")
      (node (ref "U19") (pin "56") (pinfunction "PE11_56") (pintype "bidirectional"))
    )
    (net (code "109") (name "unconnected-(U19-PE12-Pad57)") (class "Default")
      (node (ref "U19") (pin "57") (pinfunction "PE12_57") (pintype "bidirectional"))
    )
    (net (code "110") (name "unconnected-(U19-PE13-Pad58)") (class "Default")
      (node (ref "U19") (pin "58") (pinfunction "PE13_58") (pintype "bidirectional"))
    )
    (net (code "111") (name "unconnected-(U19-PE14-Pad59)") (class "Default")
      (node (ref "U19") (pin "59") (pinfunction "PE14_59") (pintype "bidirectional"))
    )
    (net (code "112") (name "unconnected-(U19-PE15-Pad60)") (class "Default")
      (node (ref "U19") (pin "60") (pinfunction "PE15_60") (pintype "bidirectional"))
    )
    (net (code "113") (name "unconnected-(U19-PF0-Pad77)") (class "Default")
      (node (ref "U19") (pin "77") (pinfunction "PF0_77") (pintype "bidirectional"))
    )
    (net (code "114") (name "unconnected-(U19-PF1-Pad78)") (class "Default")
      (node (ref "U19") (pin "78") (pinfunction "PF1_78") (pintype "bidirectional"))
    )
    (net (code "115") (name "unconnected-(U19-PF2-Pad79)") (class "Default")
      (node (ref "U19") (pin "79") (pinfunction "PF2_79") (pintype "bidirectional"))
    )
    (net (code "116") (name "unconnected-(U19-PF3-Pad108)") (class "Default")
      (node (ref "U19") (pin "108") (pinfunction "PF3_108") (pintype "bidirectional"))
    )
    (net (code "117") (name "unconnected-(U19-PF4-Pad109)") (class "Default")
      (node (ref "U19") (pin "109") (pinfunction "PF4_109") (pintype "bidirectional"))
    )
    (net (code "118") (name "unconnected-(U19-PF5-Pad110)") (class "Default")
      (node (ref "U19") (pin "110") (pinfunction "PF5_110") (pintype "bidirectional"))
    )
    (net (code "119") (name "unconnected-(U19-PF8{slash}HSADC4-Pad19)") (class "Default")
      (node (ref "U19") (pin "19") (pinfunction "PF8/HSADC4_19") (pintype "bidirectional"))
    )
    (net (code "120") (name "unconnected-(U19-PF9{slash}HSADC5-Pad20)") (class "Default")
      (node (ref "U19") (pin "20") (pinfunction "PF9/HSADC5_20") (pintype "bidirectional"))
    )
    (net (code "121") (name "unconnected-(U19-PF10{slash}HSADC6-Pad21)") (class "Default")
      (node (ref "U19") (pin "21") (pinfunction "PF10/HSADC6_21") (pintype "bidirectional"))
    )
    (net (code "122") (name "unconnected-(U19-PF11{slash}OP2_P1-Pad48)") (class "Default")
      (node (ref "U19") (pin "48") (pinfunction "PF11/OP2_P1_48") (pintype "bidirectional"))
    )
    (net (code "123") (name "unconnected-(U19-PF12{slash}OP2_N1-Pad49)") (class "Default")
      (node (ref "U19") (pin "49") (pinfunction "PF12/OP2_N1_49") (pintype "bidirectional"))
    )
    (net (code "124") (name "unconnected-(U19-PF13-Pad50)") (class "Default")
      (node (ref "U19") (pin "50") (pinfunction "PF13_50") (pintype "bidirectional"))
    )
    (net (code "125") (name "unconnected-(U19-PF14-Pad113)") (class "Default")
      (node (ref "U19") (pin "113") (pinfunction "PF14_113") (pintype "bidirectional"))
    )
    (net (code "126") (name "unconnected-(U19-XO-Pad24)") (class "Default")
      (node (ref "U19") (pin "24") (pinfunction "XO_24") (pintype "bidirectional"))
    )
  )
)
